# PiZeroDaughterBoardScamatic.net
KiCad netlist of a schematic drawn in Altium Designer
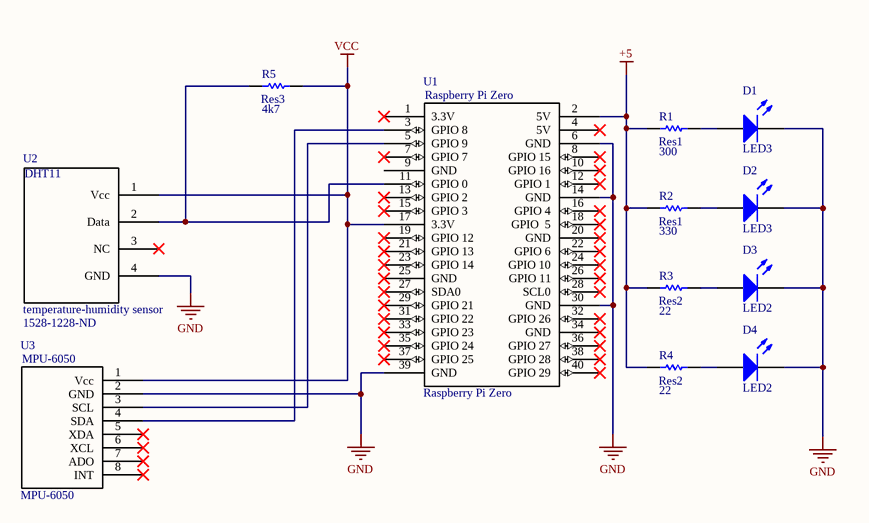
[diagram p0: PiZeroDaughterBoardScamatic.SchDoc]

(export (version "E")
  (design (tool "Eeschema 10.0.6"))
  (components
    (comp (ref "D1")
      (value "LED3")
      (footprint "LEDRD254W57D500H1070")
      (description "Typical BLUE SiC LED")
      (fields (field (name "PUBLISHER") "Altium Limited"))
      (libsource (lib "Miscellaneous Devices") (part "LED3"))
    )
    (comp (ref "D2")
      (value "LED3")
      (footprint "LEDRD254W57D500H1070")
      (description "Typical BLUE SiC LED")
      (fields (field (name "PUBLISHER") "Altium Limited"))
      (libsource (lib "Miscellaneous Devices") (part "LED3"))
    )
    (comp (ref "D3")
      (value "LED2")
      (footprint "LEDRD254W57D500H1070")
      (description "GREEN LED")
      (fields (field (name "PUBLISHER") "Altium Limited"))
      (libsource (lib "Miscellaneous Devices") (part "LED2"))
    )
    (comp (ref "D4")
      (value "LED2")
      (footprint "LEDRD254W57D500H1070")
      (description "GREEN LED")
      (fields (field (name "PUBLISHER") "Altium Limited"))
      (libsource (lib "Miscellaneous Devices") (part "LED2"))
    )
    (comp (ref "R1")
      (value "Res1")
      (footprint "AXIAL-0.3")
      (description "Resistor")
      (fields (field (name "ALTIUM_VALUE") "300") (field (name "PUBLISHER") "Altium Limited"))
      (libsource (lib "Miscellaneous Devices") (part "Res1"))
    )
    (comp (ref "R2")
      (value "Res1")
      (footprint "AXIAL-0.3")
      (description "Resistor")
      (fields (field (name "ALTIUM_VALUE") "330") (field (name "PUBLISHER") "Altium Limited"))
      (libsource (lib "Miscellaneous Devices") (part "Res1"))
    )
    (comp (ref "R3")
      (value "Res2")
      (footprint "AXIAL-0.3")
      (description "Resistor")
      (fields (field (name "ALTIUM_VALUE") "22") (field (name "PUBLISHER") "Altium Limited"))
      (libsource (lib "Miscellaneous Devices") (part "Res1"))
    )
    (comp (ref "R4")
      (value "Res2")
      (footprint "AXIAL-0.3")
      (description "Resistor")
      (fields (field (name "ALTIUM_VALUE") "22") (field (name "PUBLISHER") "Altium Limited"))
      (libsource (lib "Miscellaneous Devices") (part "Res1"))
    )
    (comp (ref "R5")
      (value "Res3")
      (footprint "AXIAL-0.3")
      (description "Resistor")
      (fields (field (name "ALTIUM_VALUE") "4k7") (field (name "PUBLISHER") "Altium Limited"))
      (libsource (lib "Miscellaneous Devices") (part "Res1"))
    )
    (comp (ref "U1")
      (value "Raspberry Pi Zero")
      (footprint "ADA3708_RPI-ZERO")
      (libsource (lib "PiZeroSchematicLibary") (part "Raspberry Pi Zero"))
    )
    (comp (ref "U2")
      (value "temperature-humidity sensor")
      (footprint "NPSIP4A")
      (description "temperature-humidity sensor In out of Vcc, DQ, NC, GND")
      (fields (field (name "SUPPLIER PART NUMBER 1") "1528-1228-ND"))
      (libsource (lib "PiZeroSchematicLibary") (part "DHT11"))
    )
    (comp (ref "U3")
      (value "MPU-6050")
      (footprint "HDR1X8H")
      (description "3-axis Gyroscope, 3-axis Accelerometer.")
      (libsource (lib "PiZeroSchematicLibary") (part "MPU-6050"))
    )
  )
  (nets
    (net (code "1") (name "+5") (class "Default")
      (node (ref "R1") (pin "1") (pinfunction "1_1") (pintype "passive"))
      (node (ref "R2") (pin "1") (pinfunction "1_1") (pintype "passive"))
      (node (ref "R3") (pin "1") (pinfunction "1_1") (pintype "passive"))
      (node (ref "R4") (pin "1") (pinfunction "1_1") (pintype "passive"))
      (node (ref "U1") (pin "2") (pinfunction "5V_2") (pintype "power_in"))
    )
    (net (code "2") (name "GND") (class "Default")
      (node (ref "D1") (pin "2") (pinfunction "K_2") (pintype "passive"))
      (node (ref "D2") (pin "2") (pinfunction "K_2") (pintype "passive"))
      (node (ref "D3") (pin "2") (pinfunction "K_2") (pintype "passive"))
      (node (ref "D4") (pin "2") (pinfunction "K_2") (pintype "passive"))
      (node (ref "U1") (pin "14") (pinfunction "GND_14") (pintype "passive"))
      (node (ref "U1") (pin "30") (pinfunction "GND_30") (pintype "power_in"))
      (node (ref "U1") (pin "39") (pinfunction "GND_39") (pintype "power_in"))
      (node (ref "U1") (pin "6") (pinfunction "GND_6") (pintype "passive"))
      (node (ref "U2") (pin "4") (pinfunction "GND_4") (pintype "passive"))
      (node (ref "U3") (pin "2") (pinfunction "GND_2") (pintype "passive"))
    )
    (net (code "3") (name "Net-(D1-A)") (class "Default")
      (node (ref "D1") (pin "1") (pinfunction "A_1") (pintype "passive"))
      (node (ref "R1") (pin "2") (pinfunction "2_2") (pintype "passive"))
    )
    (net (code "4") (name "Net-(D2-A)") (class "Default")
      (node (ref "D2") (pin "1") (pinfunction "A_1") (pintype "passive"))
      (node (ref "R2") (pin "2") (pinfunction "2_2") (pintype "passive"))
    )
    (net (code "5") (name "Net-(D3-A)") (class "Default")
      (node (ref "D3") (pin "1") (pinfunction "A_1") (pintype "passive"))
      (node (ref "R3") (pin "2") (pinfunction "2_2") (pintype "passive"))
    )
    (net (code "6") (name "Net-(D4-A)") (class "Default")
      (node (ref "D4") (pin "1") (pinfunction "A_1") (pintype "passive"))
      (node (ref "R4") (pin "2") (pinfunction "2_2") (pintype "passive"))
    )
    (net (code "7") (name "Net-(U1-GPIO_0)") (class "Default")
      (node (ref "R5") (pin "1") (pinfunction "1_1") (pintype "passive"))
      (node (ref "U1") (pin "11") (pinfunction "GPIO_0_11") (pintype "bidirectional"))
      (node (ref "U2") (pin "2") (pinfunction "Data_2") (pintype "passive"))
    )
    (net (code "8") (name "Net-(U1-GPIO_8)") (class "Default")
      (node (ref "U1") (pin "3") (pinfunction "GPIO_8_3") (pintype "bidirectional"))
      (node (ref "U3") (pin "4") (pinfunction "SDA_4") (pintype "passive"))
    )
    (net (code "9") (name "Net-(U1-GPIO_9)") (class "Default")
      (node (ref "U1") (pin "5") (pinfunction "GPIO_9_5") (pintype "bidirectional"))
      (node (ref "U3") (pin "3") (pinfunction "SCL_3") (pintype "passive"))
    )
    (net (code "10") (name "VCC") (class "Default")
      (node (ref "R5") (pin "2") (pinfunction "2_2") (pintype "passive"))
      (node (ref "U1") (pin "17") (pinfunction "3.3V_17") (pintype "power_in"))
      (node (ref "U2") (pin "1") (pinfunction "Vcc_1") (pintype "passive"))
      (node (ref "U3") (pin "1") (pinfunction "Vcc_1") (pintype "passive"))
    )
    (net (code "11") (name "unconnected-(U1-3.3V-Pad1)") (class "Default")
      (node (ref "U1") (pin "1") (pinfunction "3.3V_1") (pintype "power_in+no_connect"))
    )
    (net (code "12") (name "unconnected-(U1-5V-Pad4)") (class "Default")
      (node (ref "U1") (pin "4") (pinfunction "5V_4") (pintype "power_in+no_connect"))
    )
    (net (code "13") (name "unconnected-(U1-GND-Pad9)") (class "Default")
      (node (ref "U1") (pin "9") (pinfunction "GND_9") (pintype "passive"))
    )
    (net (code "14") (name "unconnected-(U1-GND-Pad20)") (class "Default")
      (node (ref "U1") (pin "20") (pinfunction "GND_20") (pintype "passive+no_connect"))
    )
    (net (code "15") (name "unconnected-(U1-GND-Pad25)") (class "Default")
      (node (ref "U1") (pin "25") (pinfunction "GND_25") (pintype "passive+no_connect"))
    )
    (net (code "16") (name "unconnected-(U1-GND-Pad34)") (class "Default")
      (node (ref "U1") (pin "34") (pinfunction "GND_34") (pintype "power_in+no_connect"))
    )
    (net (code "17") (name "unconnected-(U1-GPIO_1-Pad12)") (class "Default")
      (node (ref "U1") (pin "12") (pinfunction "GPIO_1_12") (pintype "bidirectional+no_connect"))
    )
    (net (code "18") (name "unconnected-(U1-GPIO_2-Pad13)") (class "Default")
      (node (ref "U1") (pin "13") (pinfunction "GPIO_2_13") (pintype "bidirectional+no_connect"))
    )
    (net (code "19") (name "unconnected-(U1-GPIO_3-Pad15)") (class "Default")
      (node (ref "U1") (pin "15") (pinfunction "GPIO_3_15") (pintype "bidirectional+no_connect"))
    )
    (net (code "20") (name "unconnected-(U1-GPIO_4-Pad16)") (class "Default")
      (node (ref "U1") (pin "16") (pinfunction "GPIO_4_16") (pintype "bidirectional+no_connect"))
    )
    (net (code "21") (name "unconnected-(U1-GPIO_6-Pad22)") (class "Default")
      (node (ref "U1") (pin "22") (pinfunction "GPIO_6_22") (pintype "bidirectional+no_connect"))
    )
    (net (code "22") (name "unconnected-(U1-GPIO_7-Pad7)") (class "Default")
      (node (ref "U1") (pin "7") (pinfunction "GPIO_7_7") (pintype "bidirectional+no_connect"))
    )
    (net (code "23") (name "unconnected-(U1-GPIO_10-Pad24)") (class "Default")
      (node (ref "U1") (pin "24") (pinfunction "GPIO_10_24") (pintype "bidirectional+no_connect"))
    )
    (net (code "24") (name "unconnected-(U1-GPIO_11-Pad26)") (class "Default")
      (node (ref "U1") (pin "26") (pinfunction "GPIO_11_26") (pintype "bidirectional+no_connect"))
    )
    (net (code "25") (name "unconnected-(U1-GPIO_12-Pad19)") (class "Default")
      (node (ref "U1") (pin "19") (pinfunction "GPIO_12_19") (pintype "bidirectional+no_connect"))
    )
    (net (code "26") (name "unconnected-(U1-GPIO_13-Pad21)") (class "Default")
      (node (ref "U1") (pin "21") (pinfunction "GPIO_13_21") (pintype "bidirectional+no_connect"))
    )
    (net (code "27") (name "unconnected-(U1-GPIO_14-Pad23)") (class "Default")
      (node (ref "U1") (pin "23") (pinfunction "GPIO_14_23") (pintype "bidirectional+no_connect"))
    )
    (net (code "28") (name "unconnected-(U1-GPIO_15-Pad8)") (class "Default")
      (node (ref "U1") (pin "8") (pinfunction "GPIO_15_8") (pintype "bidirectional+no_connect"))
    )
    (net (code "29") (name "unconnected-(U1-GPIO_16-Pad10)") (class "Default")
      (node (ref "U1") (pin "10") (pinfunction "GPIO_16_10") (pintype "bidirectional+no_connect"))
    )
    (net (code "30") (name "unconnected-(U1-GPIO_21-Pad29)") (class "Default")
      (node (ref "U1") (pin "29") (pinfunction "GPIO_21_29") (pintype "bidirectional+no_connect"))
    )
    (net (code "31") (name "unconnected-(U1-GPIO_22-Pad31)") (class "Default")
      (node (ref "U1") (pin "31") (pinfunction "GPIO_22_31") (pintype "bidirectional+no_connect"))
    )
    (net (code "32") (name "unconnected-(U1-GPIO_23-Pad33)") (class "Default")
      (node (ref "U1") (pin "33") (pinfunction "GPIO_23_33") (pintype "bidirectional+no_connect"))
    )
    (net (code "33") (name "unconnected-(U1-GPIO_24-Pad35)") (class "Default")
      (node (ref "U1") (pin "35") (pinfunction "GPIO_24_35") (pintype "bidirectional+no_connect"))
    )
    (net (code "34") (name "unconnected-(U1-GPIO_25-Pad37)") (class "Default")
      (node (ref "U1") (pin "37") (pinfunction "GPIO_25_37") (pintype "bidirectional+no_connect"))
    )
    (net (code "35") (name "unconnected-(U1-GPIO_26-Pad32)") (class "Default")
      (node (ref "U1") (pin "32") (pinfunction "GPIO_26_32") (pintype "bidirectional+no_connect"))
    )
    (net (code "36") (name "unconnected-(U1-GPIO_27-Pad36)") (class "Default")
      (node (ref "U1") (pin "36") (pinfunction "GPIO_27_36") (pintype "bidirectional+no_connect"))
    )
    (net (code "37") (name "unconnected-(U1-GPIO_28-Pad38)") (class "Default")
      (node (ref "U1") (pin "38") (pinfunction "GPIO_28_38") (pintype "bidirectional+no_connect"))
    )
    (net (code "38") (name "unconnected-(U1-GPIO_29-Pad40)") (class "Default")
      (node (ref "U1") (pin "40") (pinfunction "GPIO_29_40") (pintype "bidirectional+no_connect"))
    )
    (net (code "39") (name "unconnected-(U1-GPIO__5-Pad18)") (class "Default")
      (node (ref "U1") (pin "18") (pinfunction "GPIO__5_18") (pintype "bidirectional+no_connect"))
    )
    (net (code "40") (name "unconnected-(U1-SCL0-Pad28)") (class "Default")
      (node (ref "U1") (pin "28") (pinfunction "SCL0_28") (pintype "bidirectional+no_connect"))
    )
    (net (code "41") (name "unconnected-(U1-SDA0-Pad27)") (class "Default")
      (node (ref "U1") (pin "27") (pinfunction "SDA0_27") (pintype "bidirectional+no_connect"))
    )
    (net (code "42") (name "unconnected-(U2-NC-Pad3)") (class "Default")
      (node (ref "U2") (pin "3") (pinfunction "NC_3") (pintype "passive+no_connect"))
    )
    (net (code "43") (name "unconnected-(U3-ADO-Pad7)") (class "Default")
      (node (ref "U3") (pin "7") (pinfunction "ADO_7") (pintype "passive+no_connect"))
    )
    (net (code "44") (name "unconnected-(U3-INT-Pad8)") (class "Default")
      (node (ref "U3") (pin "8") (pinfunction "INT_8") (pintype "passive+no_connect"))
    )
    (net (code "45") (name "unconnected-(U3-XCL-Pad6)") (class "Default")
      (node (ref "U3") (pin "6") (pinfunction "XCL_6") (pintype "passive+no_connect"))
    )
    (net (code "46") (name "unconnected-(U3-XDA-Pad5)") (class "Default")
      (node (ref "U3") (pin "5") (pinfunction "XDA_5") (pintype "passive+no_connect"))
    )
  )
)
